# Sheet1.net
KiCad netlist of a schematic drawn in Altium Designer
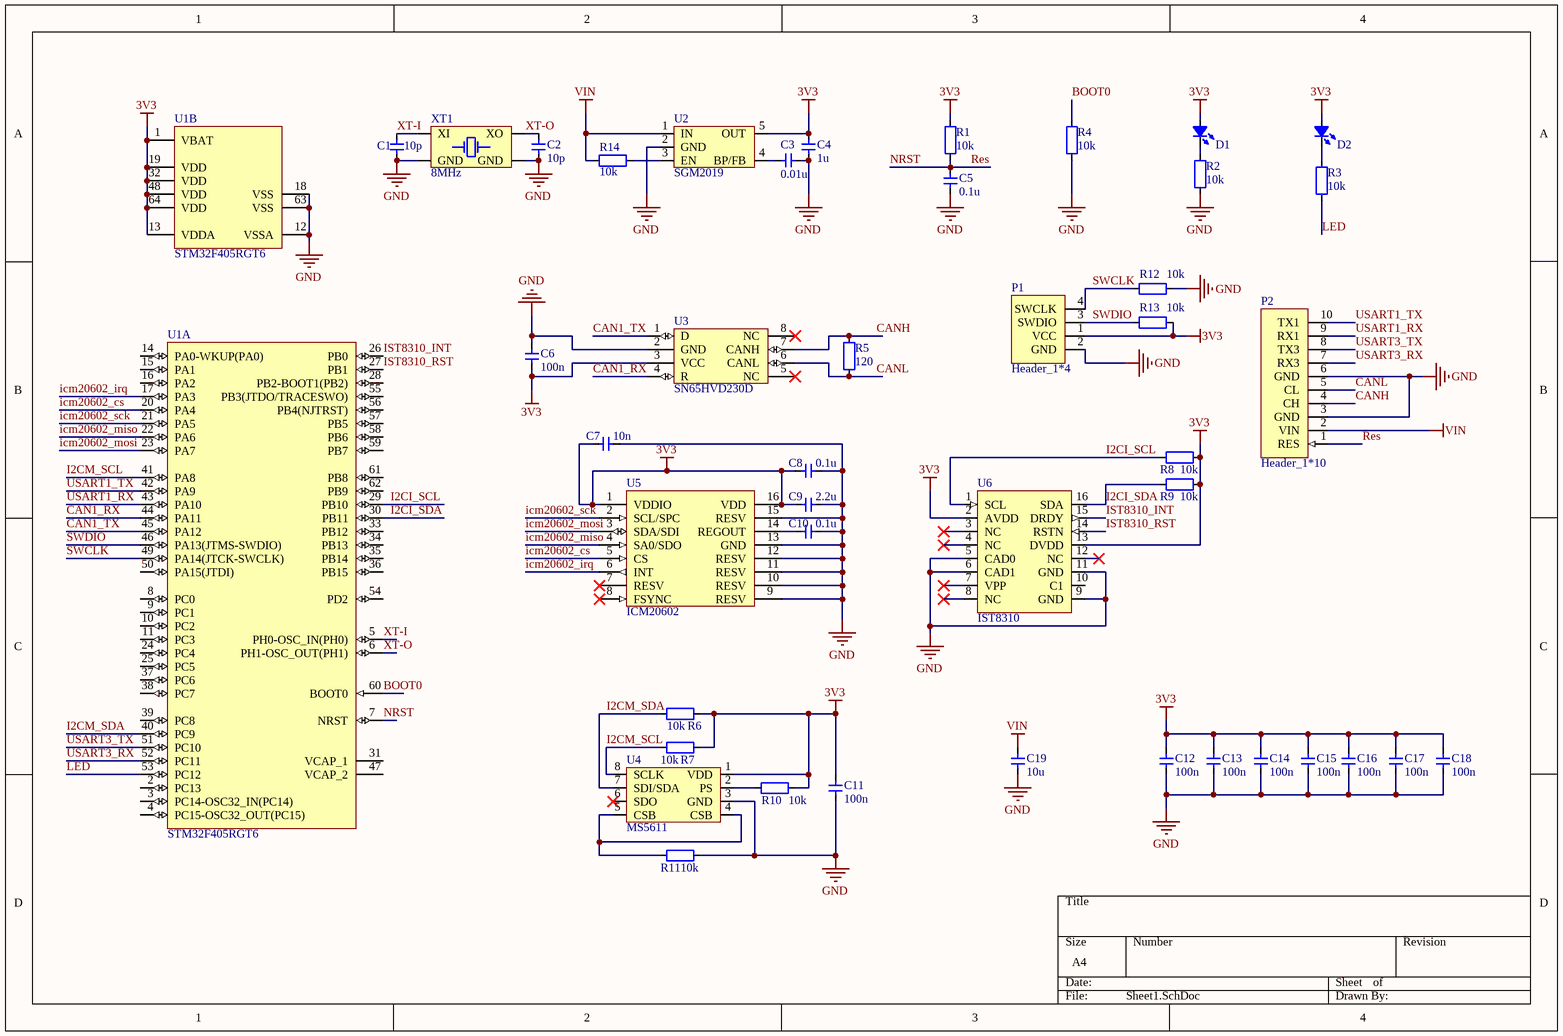
[diagram p0: Sheet1.SchDoc]

(export (version "E")
  (design (tool "Eeschema 10.0.6"))
  (components
    (comp (ref "C1")
      (value "10p")
      (footprint "CAP_0603")
      (description "Capacitor")
      (fields (field (name "Comment") "Cap_0603"))
      (libsource (lib "Schlib1") (part "Cap_0603"))
    )
    (comp (ref "C2")
      (value "10p")
      (footprint "CAP_0603")
      (description "Capacitor")
      (fields (field (name "Comment") "Cap_0603"))
      (libsource (lib "Schlib1") (part "Cap_0603"))
    )
    (comp (ref "C3")
      (value "0.01u")
      (footprint "CAP_0603")
      (description "Capacitor")
      (fields (field (name "Comment") "Cap_0603"))
      (libsource (lib "Schlib1") (part "Cap_0603"))
    )
    (comp (ref "C4")
      (value "1u")
      (footprint "CAP_0603")
      (description "Capacitor")
      (fields (field (name "Comment") "Cap_0603"))
      (libsource (lib "Schlib1") (part "Cap_0603"))
    )
    (comp (ref "C5")
      (value "0.1u")
      (footprint "CAP_0603")
      (description "Capacitor")
      (fields (field (name "Comment") "Cap_0603"))
      (libsource (lib "Schlib1") (part "Cap_0603"))
    )
    (comp (ref "C6")
      (value "100n")
      (footprint "CAP_0603")
      (description "Capacitor")
      (fields (field (name "Comment") "Cap_0603"))
      (libsource (lib "Schlib1") (part "Cap_0603"))
    )
    (comp (ref "C7")
      (value "10n")
      (footprint "CAP_0603")
      (description "Capacitor")
      (fields (field (name "Comment") "Cap_0603"))
      (libsource (lib "Schlib1") (part "Cap_0603"))
    )
    (comp (ref "C8")
      (value "0.1u")
      (footprint "CAP_0603")
      (description "Capacitor")
      (fields (field (name "Comment") "Cap_0603"))
      (libsource (lib "Schlib1") (part "Cap_0603"))
    )
    (comp (ref "C9")
      (value "2.2u")
      (footprint "CAP_0603")
      (description "Capacitor")
      (fields (field (name "Comment") "Cap_0603"))
      (libsource (lib "Schlib1") (part "Cap_0603"))
    )
    (comp (ref "C10")
      (value "0.1u")
      (footprint "CAP_0603")
      (description "Capacitor")
      (fields (field (name "Comment") "Cap_0603"))
      (libsource (lib "Schlib1") (part "Cap_0603"))
    )
    (comp (ref "C11")
      (value "100n")
      (footprint "CAP_0603")
      (description "Capacitor")
      (fields (field (name "Comment") "Cap_0603"))
      (libsource (lib "Schlib1") (part "Cap_0603"))
    )
    (comp (ref "C12")
      (value "100n")
      (footprint "CAP_0603")
      (description "Capacitor")
      (fields (field (name "Comment") "Cap_0603"))
      (libsource (lib "Schlib1") (part "Cap_0603"))
    )
    (comp (ref "C13")
      (value "100n")
      (footprint "CAP_0603")
      (description "Capacitor")
      (fields (field (name "Comment") "Cap_0603"))
      (libsource (lib "Schlib1") (part "Cap_0603"))
    )
    (comp (ref "C14")
      (value "100n")
      (footprint "CAP_0603")
      (description "Capacitor")
      (fields (field (name "Comment") "Cap_0603"))
      (libsource (lib "Schlib1") (part "Cap_0603"))
    )
    (comp (ref "C15")
      (value "100n")
      (footprint "CAP_0603")
      (description "Capacitor")
      (fields (field (name "Comment") "Cap_0603"))
      (libsource (lib "Schlib1") (part "Cap_0603"))
    )
    (comp (ref "C16")
      (value "100n")
      (footprint "CAP_0603")
      (description "Capacitor")
      (fields (field (name "Comment") "Cap_0603"))
      (libsource (lib "Schlib1") (part "Cap_0603"))
    )
    (comp (ref "C17")
      (value "100n")
      (footprint "CAP_0603")
      (description "Capacitor")
      (fields (field (name "Comment") "Cap_0603"))
      (libsource (lib "Schlib1") (part "Cap_0603"))
    )
    (comp (ref "C18")
      (value "100n")
      (footprint "CAP_0603")
      (description "Capacitor")
      (fields (field (name "Comment") "Cap_0603"))
      (libsource (lib "Schlib1") (part "Cap_0603"))
    )
    (comp (ref "C19")
      (value "10u")
      (footprint "CAP_0805")
      (description "Capacitor")
      (fields (field (name "Comment") "Cap_0805"))
      (libsource (lib "Schlib1") (part "Cap_0805"))
    )
    (comp (ref "D1")
      (value "LED_0603")
      (footprint "LED_0603")
      (description "LED")
      (libsource (lib "Schlib1") (part "LED_0603"))
    )
    (comp (ref "D2")
      (value "LED_0603")
      (footprint "LED_0603")
      (description "LED")
      (libsource (lib "Schlib1") (part "LED_0603"))
    )
    (comp (ref "P1")
      (value "Header_1*4")
      (footprint "HDR1*4")
      (libsource (lib "Schlib1") (part "Header_1*4"))
    )
    (comp (ref "P2")
      (value "Header_1*10")
      (footprint "HDR1*10")
      (libsource (lib "Schlib1") (part "Header_1*10"))
    )
    (comp (ref "R1")
      (value "10k")
      (footprint "RES_0603")
      (description "Resistor")
      (fields (field (name "Comment") "Res_0603"))
      (libsource (lib "") (part "Res_0603_2"))
    )
    (comp (ref "R2")
      (value "10k")
      (footprint "RES_0603")
      (description "Resistor")
      (fields (field (name "Comment") "Res_0603"))
      (libsource (lib "") (part "Res_0603_2"))
    )
    (comp (ref "R3")
      (value "10k")
      (footprint "RES_0603")
      (description "Resistor")
      (fields (field (name "Comment") "Res_0603"))
      (libsource (lib "") (part "Res_0603_2"))
    )
    (comp (ref "R4")
      (value "10k")
      (footprint "RES_0603")
      (description "Resistor")
      (fields (field (name "Comment") "Res_0603"))
      (libsource (lib "") (part "Res_0603_2"))
    )
    (comp (ref "R5")
      (value "120")
      (footprint "RES_0603")
      (description "Resistor")
      (fields (field (name "Comment") "Res_0603"))
      (libsource (lib "") (part "Res_0603_2"))
    )
    (comp (ref "R6")
      (value "10k")
      (footprint "RES_0603")
      (description "Resistor")
      (fields (field (name "Comment") "Res_0603"))
      (libsource (lib "Schlib1") (part "Res_0603"))
    )
    (comp (ref "R7")
      (value "10k")
      (footprint "RES_0603")
      (description "Resistor")
      (fields (field (name "Comment") "Res_0603"))
      (libsource (lib "Schlib1") (part "Res_0603"))
    )
    (comp (ref "R8")
      (value "10k")
      (footprint "RES_0603")
      (description "Resistor")
      (fields (field (name "Comment") "Res_0603"))
      (libsource (lib "Schlib1") (part "Res_0603"))
    )
    (comp (ref "R9")
      (value "10k")
      (footprint "RES_0603")
      (description "Resistor")
      (fields (field (name "Comment") "Res_0603"))
      (libsource (lib "Schlib1") (part "Res_0603"))
    )
    (comp (ref "R10")
      (value "10k")
      (footprint "RES_0603")
      (description "Resistor")
      (fields (field (name "Comment") "Res_0603"))
      (libsource (lib "Schlib1") (part "Res_0603"))
    )
    (comp (ref "R11")
      (value "10k")
      (footprint "RES_0603")
      (description "Resistor")
      (fields (field (name "Comment") "Res_0603"))
      (libsource (lib "Schlib1") (part "Res_0603"))
    )
    (comp (ref "R12")
      (value "10k")
      (footprint "RES_0603")
      (description "Resistor")
      (fields (field (name "Comment") "Res_0603"))
      (libsource (lib "") (part "Res_0603_1"))
    )
    (comp (ref "R13")
      (value "10k")
      (footprint "RES_0603")
      (description "Resistor")
      (fields (field (name "Comment") "Res_0603"))
      (libsource (lib "") (part "Res_0603_1"))
    )
    (comp (ref "R14")
      (value "10k")
      (footprint "RES_0603")
      (description "Resistor")
      (fields (field (name "Comment") "Res_0603"))
      (libsource (lib "Schlib1") (part "Res_0603"))
    )
    (comp (ref "U1")
      (value "STM32F405RGT6")
      (footprint "STM-LQFP64_N")
      (fields (field (name "MANUFACTURER") "STMicroelectronics"))
      (libsource (lib "STMicroelectronics STM32 F4") (part "STM32F405RGT6"))
    )
    (comp (ref "U2") (value "SGM2019") (footprint "SGM2019") (libsource (lib "Schlib1") (part "SGM2019")))
    (comp (ref "U3")
      (value "SN65HVD230D")
      (footprint "SN65HVD230")
      (libsource (lib "Schlib1") (part "SN65HVD230D"))
    )
    (comp (ref "U4") (value "MS5611") (footprint "MS5611") (libsource (lib "Schlib1") (part "MS5611")))
    (comp (ref "U5") (value "ICM20602") (footprint "ICM20602") (libsource (lib "Schlib1") (part "ICM20602")))
    (comp (ref "U6") (value "IST8310") (footprint "IST8310") (libsource (lib "Schlib1") (part "IST8310")))
    (comp (ref "XT1")
      (value "8MHz")
      (footprint "XT_2520_4")
      (description "Crystal Oscillator")
      (fields (field (name "Comment") "XTAL_2520_4P"))
      (libsource (lib "Schlib1") (part "XTAL_2520_4P"))
    )
  )
  (nets
    (net (code "1") (name "/BOOT0") (class "Default")
      (node (ref "R4") (pin "1") (pinfunction "1_1") (pintype "passive"))
      (node (ref "U1") (pin "60") (pinfunction "BOOT0_60") (pintype "input"))
    )
    (net (code "2") (name "/CAN1_RX") (class "Default")
      (node (ref "U1") (pin "44") (pinfunction "PA11_44") (pintype "bidirectional"))
      (node (ref "U3") (pin "4") (pinfunction "R_4") (pintype "bidirectional"))
    )
    (net (code "3") (name "/CAN1_TX") (class "Default")
      (node (ref "U1") (pin "45") (pinfunction "PA12_45") (pintype "bidirectional"))
      (node (ref "U3") (pin "1") (pinfunction "D_1") (pintype "bidirectional"))
    )
    (net (code "4") (name "/CANH") (class "Default")
      (node (ref "P2") (pin "4") (pinfunction "CH_4") (pintype "passive"))
      (node (ref "R5") (pin "1") (pinfunction "1_1") (pintype "passive"))
      (node (ref "U3") (pin "7") (pinfunction "CANH_7") (pintype "bidirectional"))
    )
    (net (code "5") (name "/CANL") (class "Default")
      (node (ref "P2") (pin "5") (pinfunction "CL_5") (pintype "passive"))
      (node (ref "R5") (pin "2") (pinfunction "2_2") (pintype "passive"))
      (node (ref "U3") (pin "6") (pinfunction "CANL_6") (pintype "bidirectional"))
    )
    (net (code "6") (name "/I2CI_SCL") (class "Default")
      (node (ref "R8") (pin "1") (pinfunction "1_1") (pintype "passive"))
      (node (ref "U1") (pin "29") (pinfunction "PB10_29") (pintype "bidirectional"))
      (node (ref "U6") (pin "1") (pinfunction "SCL_1") (pintype "input"))
    )
    (net (code "7") (name "/I2CI_SDA") (class "Default")
      (node (ref "R9") (pin "1") (pinfunction "1_1") (pintype "passive"))
      (node (ref "U1") (pin "30") (pinfunction "PB11_30") (pintype "bidirectional"))
      (node (ref "U6") (pin "16") (pinfunction "SDA_16") (pintype "bidirectional"))
    )
    (net (code "8") (name "/I2CM_SCL") (class "Default")
      (node (ref "R7") (pin "1") (pinfunction "1_1") (pintype "passive"))
      (node (ref "U1") (pin "41") (pinfunction "PA8_41") (pintype "bidirectional"))
      (node (ref "U4") (pin "8") (pinfunction "SCLK_8") (pintype "passive"))
    )
    (net (code "9") (name "/I2CM_SDA") (class "Default")
      (node (ref "R6") (pin "1") (pinfunction "1_1") (pintype "passive"))
      (node (ref "U1") (pin "40") (pinfunction "PC9_40") (pintype "bidirectional"))
      (node (ref "U4") (pin "7") (pinfunction "SDI/SDA_7") (pintype "passive"))
    )
    (net (code "10") (name "/IST8310_INT") (class "Default")
      (node (ref "U1") (pin "26") (pinfunction "PB0_26") (pintype "bidirectional"))
      (node (ref "U6") (pin "15") (pinfunction "DRDY_15") (pintype "output"))
    )
    (net (code "11") (name "/IST8310_RST") (class "Default")
      (node (ref "U1") (pin "27") (pinfunction "PB1_27") (pintype "bidirectional"))
      (node (ref "U6") (pin "14") (pinfunction "RSTN_14") (pintype "input"))
    )
    (net (code "12") (name "/LED") (class "Default")
      (node (ref "R3") (pin "2") (pinfunction "2_2") (pintype "passive"))
      (node (ref "U1") (pin "53") (pinfunction "PC12_53") (pintype "bidirectional"))
    )
    (net (code "13") (name "/NRST") (class "Default")
      (node (ref "C5") (pin "2") (pinfunction "2_2") (pintype "passive"))
      (node (ref "P2") (pin "1") (pinfunction "RES_1") (pintype "input"))
      (node (ref "R1") (pin "2") (pinfunction "2_2") (pintype "passive"))
      (node (ref "U1") (pin "7") (pinfunction "NRST_7") (pintype "bidirectional"))
    )
    (net (code "14") (name "/SWCLK") (class "Default")
      (node (ref "P1") (pin "4") (pinfunction "SWCLK_4") (pintype "passive"))
      (node (ref "R12") (pin "2") (pinfunction "2_2") (pintype "passive"))
      (node (ref "U1") (pin "49") (pinfunction "PA14(JTCK-SWCLK)_49") (pintype "bidirectional"))
    )
    (net (code "15") (name "/SWDIO") (class "Default")
      (node (ref "P1") (pin "3") (pinfunction "SWDIO_3") (pintype "passive"))
      (node (ref "R13") (pin "2") (pinfunction "2_2") (pintype "passive"))
      (node (ref "U1") (pin "46") (pinfunction "PA13(JTMS-SWDIO)_46") (pintype "bidirectional"))
    )
    (net (code "16") (name "/USART1_RX") (class "Default")
      (node (ref "P2") (pin "9") (pinfunction "RX1_9") (pintype "passive"))
      (node (ref "U1") (pin "43") (pinfunction "PA10_43") (pintype "bidirectional"))
    )
    (net (code "17") (name "/USART1_TX") (class "Default")
      (node (ref "P2") (pin "10") (pinfunction "TX1_10") (pintype "passive"))
      (node (ref "U1") (pin "42") (pinfunction "PA9_42") (pintype "bidirectional"))
    )
    (net (code "18") (name "/USART3_RX") (class "Default")
      (node (ref "P2") (pin "7") (pinfunction "RX3_7") (pintype "passive"))
      (node (ref "U1") (pin "52") (pinfunction "PC11_52") (pintype "bidirectional"))
    )
    (net (code "19") (name "/USART3_TX") (class "Default")
      (node (ref "P2") (pin "8") (pinfunction "TX3_8") (pintype "passive"))
      (node (ref "U1") (pin "51") (pinfunction "PC10_51") (pintype "bidirectional"))
    )
    (net (code "20") (name "/XT-I") (class "Default")
      (node (ref "C1") (pin "2") (pinfunction "2_2") (pintype "passive"))
      (node (ref "U1") (pin "5") (pinfunction "PH0-OSC_IN(PH0)_5") (pintype "bidirectional"))
      (node (ref "XT1") (pin "1") (pinfunction "XI_1") (pintype "passive"))
    )
    (net (code "21") (name "/XT-O") (class "Default")
      (node (ref "C2") (pin "2") (pinfunction "2_2") (pintype "passive"))
      (node (ref "U1") (pin "6") (pinfunction "PH1-OSC_OUT(PH1)_6") (pintype "bidirectional"))
      (node (ref "XT1") (pin "3") (pinfunction "XO_3") (pintype "passive"))
    )
    (net (code "22") (name "/icm20602_cs") (class "Default")
      (node (ref "U1") (pin "20") (pinfunction "PA4_20") (pintype "bidirectional"))
      (node (ref "U5") (pin "5") (pinfunction "CS_5") (pintype "input"))
    )
    (net (code "23") (name "/icm20602_irq") (class "Default")
      (node (ref "U1") (pin "17") (pinfunction "PA3_17") (pintype "bidirectional"))
      (node (ref "U5") (pin "6") (pinfunction "INT_6") (pintype "output"))
    )
    (net (code "24") (name "/icm20602_miso") (class "Default")
      (node (ref "U1") (pin "22") (pinfunction "PA6_22") (pintype "bidirectional"))
      (node (ref "U5") (pin "4") (pinfunction "SA0/SDO_4") (pintype "input"))
    )
    (net (code "25") (name "/icm20602_mosi") (class "Default")
      (node (ref "U1") (pin "23") (pinfunction "PA7_23") (pintype "bidirectional"))
      (node (ref "U5") (pin "3") (pinfunction "SDA/SDI_3") (pintype "bidirectional"))
    )
    (net (code "26") (name "/icm20602_sck") (class "Default")
      (node (ref "U1") (pin "21") (pinfunction "PA5_21") (pintype "bidirectional"))
      (node (ref "U5") (pin "2") (pinfunction "SCL/SPC_2") (pintype "input"))
    )
    (net (code "27") (name "3V3") (class "Default")
      (node (ref "C11") (pin "2") (pinfunction "2_2") (pintype "passive"))
      (node (ref "C12") (pin "2") (pinfunction "2_2") (pintype "passive"))
      (node (ref "C13") (pin "2") (pinfunction "2_2") (pintype "passive"))
      (node (ref "C14") (pin "2") (pinfunction "2_2") (pintype "passive"))
      (node (ref "C15") (pin "2") (pinfunction "2_2") (pintype "passive"))
      (node (ref "C16") (pin "2") (pinfunction "2_2") (pintype "passive"))
      (node (ref "C17") (pin "2") (pinfunction "2_2") (pintype "passive"))
      (node (ref "C18") (pin "2") (pinfunction "2_2") (pintype "passive"))
      (node (ref "C4") (pin "2") (pinfunction "2_2") (pintype "passive"))
      (node (ref "C6") (pin "1") (pinfunction "1_1") (pintype "passive"))
      (node (ref "C7") (pin "2") (pinfunction "2_2") (pintype "passive"))
      (node (ref "C8") (pin "2") (pinfunction "2_2") (pintype "passive"))
      (node (ref "C9") (pin "2") (pinfunction "2_2") (pintype "passive"))
      (node (ref "D1") (pin "1") (pinfunction "A_1") (pintype "passive"))
      (node (ref "D2") (pin "1") (pinfunction "A_1") (pintype "passive"))
      (node (ref "P1") (pin "1") (pinfunction "VCC_1") (pintype "power_in"))
      (node (ref "R1") (pin "1") (pinfunction "1_1") (pintype "passive"))
      (node (ref "R10") (pin "2") (pinfunction "2_2") (pintype "passive"))
      (node (ref "R13") (pin "1") (pinfunction "1_1") (pintype "passive"))
      (node (ref "R6") (pin "2") (pinfunction "2_2") (pintype "passive"))
      (node (ref "R7") (pin "2") (pinfunction "2_2") (pintype "passive"))
      (node (ref "R8") (pin "2") (pinfunction "2_2") (pintype "passive"))
      (node (ref "R9") (pin "2") (pinfunction "2_2") (pintype "passive"))
      (node (ref "U1") (pin "1") (pinfunction "VBAT_1") (pintype "power_in"))
      (node (ref "U1") (pin "13") (pinfunction "VDDA_13") (pintype "power_in"))
      (node (ref "U1") (pin "19") (pinfunction "VDD_19") (pintype "power_in"))
      (node (ref "U1") (pin "32") (pinfunction "VDD_32") (pintype "power_in"))
      (node (ref "U1") (pin "48") (pinfunction "VDD_48") (pintype "power_in"))
      (node (ref "U1") (pin "64") (pinfunction "VDD_64") (pintype "power_in"))
      (node (ref "U2") (pin "5") (pinfunction "OUT_5") (pintype "passive"))
      (node (ref "U3") (pin "3") (pinfunction "VCC_3") (pintype "power_in"))
      (node (ref "U4") (pin "1") (pinfunction "VDD_1") (pintype "power_in"))
      (node (ref "U5") (pin "1") (pinfunction "VDDIO_1") (pintype "passive"))
      (node (ref "U5") (pin "16") (pinfunction "VDD_16") (pintype "power_in"))
      (node (ref "U6") (pin "13") (pinfunction "DVDD_13") (pintype "power_in"))
      (node (ref "U6") (pin "2") (pinfunction "AVDD_2") (pintype "power_in"))
    )
    (net (code "28") (name "GND") (class "Default")
      (node (ref "C1") (pin "1") (pinfunction "1_1") (pintype "passive"))
      (node (ref "C10") (pin "1") (pinfunction "1_1") (pintype "passive"))
      (node (ref "C11") (pin "1") (pinfunction "1_1") (pintype "passive"))
      (node (ref "C12") (pin "1") (pinfunction "1_1") (pintype "passive"))
      (node (ref "C13") (pin "1") (pinfunction "1_1") (pintype "passive"))
      (node (ref "C14") (pin "1") (pinfunction "1_1") (pintype "passive"))
      (node (ref "C15") (pin "1") (pinfunction "1_1") (pintype "passive"))
      (node (ref "C16") (pin "1") (pinfunction "1_1") (pintype "passive"))
      (node (ref "C17") (pin "1") (pinfunction "1_1") (pintype "passive"))
      (node (ref "C18") (pin "1") (pinfunction "1_1") (pintype "passive"))
      (node (ref "C19") (pin "1") (pinfunction "1_1") (pintype "passive"))
      (node (ref "C2") (pin "1") (pinfunction "1_1") (pintype "passive"))
      (node (ref "C3") (pin "1") (pinfunction "1_1") (pintype "passive"))
      (node (ref "C4") (pin "1") (pinfunction "1_1") (pintype "passive"))
      (node (ref "C5") (pin "1") (pinfunction "1_1") (pintype "passive"))
      (node (ref "C6") (pin "2") (pinfunction "2_2") (pintype "passive"))
      (node (ref "C7") (pin "1") (pinfunction "1_1") (pintype "passive"))
      (node (ref "C8") (pin "1") (pinfunction "1_1") (pintype "passive"))
      (node (ref "C9") (pin "1") (pinfunction "1_1") (pintype "passive"))
      (node (ref "P1") (pin "2") (pinfunction "GND_2") (pintype "power_in"))
      (node (ref "P2") (pin "3") (pinfunction "GND_3") (pintype "passive"))
      (node (ref "P2") (pin "6") (pinfunction "GND_6") (pintype "passive"))
      (node (ref "R11") (pin "2") (pinfunction "2_2") (pintype "passive"))
      (node (ref "R12") (pin "1") (pinfunction "1_1") (pintype "passive"))
      (node (ref "R2") (pin "2") (pinfunction "2_2") (pintype "passive"))
      (node (ref "R4") (pin "2") (pinfunction "2_2") (pintype "passive"))
      (node (ref "U1") (pin "12") (pinfunction "VSSA_12") (pintype "power_in"))
      (node (ref "U1") (pin "18") (pinfunction "VSS_18") (pintype "power_in"))
      (node (ref "U1") (pin "63") (pinfunction "VSS_63") (pintype "power_in"))
      (node (ref "U2") (pin "2") (pinfunction "GND_2") (pintype "passive"))
      (node (ref "U3") (pin "2") (pinfunction "GND_2") (pintype "power_in"))
      (node (ref "U4") (pin "3") (pinfunction "GND_3") (pintype "power_in"))
      (node (ref "U5") (pin "10") (pinfunction "RESV_10") (pintype "passive"))
      (node (ref "U5") (pin "11") (pinfunction "RESV_11") (pintype "passive"))
      (node (ref "U5") (pin "12") (pinfunction "RESV_12") (pintype "passive"))
      (node (ref "U5") (pin "13") (pinfunction "GND_13") (pintype "power_in"))
      (node (ref "U5") (pin "15") (pinfunction "RESV_15") (pintype "passive"))
      (node (ref "U5") (pin "9") (pinfunction "RESV_9") (pintype "passive"))
      (node (ref "U6") (pin "11") (pinfunction "GND_11") (pintype "power_in"))
      (node (ref "U6") (pin "5") (pinfunction "CAD0_5") (pintype "passive"))
      (node (ref "U6") (pin "6") (pinfunction "CAD1_6") (pintype "passive"))
      (node (ref "U6") (pin "9") (pinfunction "GND_9") (pintype "power_in"))
      (node (ref "XT1") (pin "2") (pinfunction "GND_2") (pintype "power_in"))
      (node (ref "XT1") (pin "4") (pinfunction "GND_4") (pintype "power_in"))
    )
    (net (code "29") (name "Net-(D1-K)") (class "Default")
      (node (ref "D1") (pin "2") (pinfunction "K_2") (pintype "passive"))
      (node (ref "R2") (pin "1") (pinfunction "1_1") (pintype "passive"))
    )
    (net (code "30") (name "Net-(D2-K)") (class "Default")
      (node (ref "D2") (pin "2") (pinfunction "K_2") (pintype "passive"))
      (node (ref "R3") (pin "1") (pinfunction "1_1") (pintype "passive"))
    )
    (net (code "31") (name "Net-(R11-Pad1)") (class "Default")
      (node (ref "R11") (pin "1") (pinfunction "1_1") (pintype "passive"))
      (node (ref "U4") (pin "4") (pinfunction "CSB_4") (pintype "passive"))
      (node (ref "U4") (pin "5") (pinfunction "CSB_5") (pintype "passive"))
    )
    (net (code "32") (name "Net-(U2-BP{slash}FB)") (class "Default")
      (node (ref "C3") (pin "2") (pinfunction "2_2") (pintype "passive"))
      (node (ref "U2") (pin "4") (pinfunction "BP/FB_4") (pintype "passive"))
    )
    (net (code "33") (name "Net-(U2-EN)") (class "Default")
      (node (ref "R14") (pin "2") (pinfunction "2_2") (pintype "passive"))
      (node (ref "U2") (pin "3") (pinfunction "EN_3") (pintype "passive"))
    )
    (net (code "34") (name "Net-(U4-PS)") (class "Default")
      (node (ref "R10") (pin "1") (pinfunction "1_1") (pintype "passive"))
      (node (ref "U4") (pin "2") (pinfunction "PS_2") (pintype "passive"))
    )
    (net (code "35") (name "Net-(U5-REGOUT)") (class "Default")
      (node (ref "C10") (pin "2") (pinfunction "2_2") (pintype "passive"))
      (node (ref "U5") (pin "14") (pinfunction "REGOUT_14") (pintype "passive"))
    )
    (net (code "36") (name "VIN") (class "Default")
      (node (ref "C19") (pin "2") (pinfunction "2_2") (pintype "passive"))
      (node (ref "P2") (pin "2") (pinfunction "VIN_2") (pintype "power_in"))
      (node (ref "R14") (pin "1") (pinfunction "1_1") (pintype "passive"))
      (node (ref "U2") (pin "1") (pinfunction "IN_1") (pintype "passive"))
    )
    (net (code "37") (name "unconnected-(U1A-PA0-WKUP(PA0)-Pad14)") (class "Default")
      (node (ref "U1") (pin "14") (pinfunction "PA0-WKUP(PA0)_14") (pintype "bidirectional"))
    )
    (net (code "38") (name "unconnected-(U1A-PA1-Pad15)") (class "Default")
      (node (ref "U1") (pin "15") (pinfunction "PA1_15") (pintype "bidirectional"))
    )
    (net (code "39") (name "unconnected-(U1A-PA2-Pad16)") (class "Default")
      (node (ref "U1") (pin "16") (pinfunction "PA2_16") (pintype "bidirectional"))
    )
    (net (code "40") (name "unconnected-(U1A-PA15(JTDI)-Pad50)") (class "Default")
      (node (ref "U1") (pin "50") (pinfunction "PA15(JTDI)_50") (pintype "bidirectional"))
    )
    (net (code "41") (name "unconnected-(U1A-PB2-BOOT1(PB2)-Pad28)") (class "Default")
      (node (ref "U1") (pin "28") (pinfunction "PB2-BOOT1(PB2)_28") (pintype "bidirectional"))
    )
    (net (code "42") (name "unconnected-(U1A-PB3(JTDO{slash}TRACESWO)-Pad55)") (class "Default")
      (node (ref "U1") (pin "55") (pinfunction "PB3(JTDO/TRACESWO)_55") (pintype "bidirectional"))
    )
    (net (code "43") (name "unconnected-(U1A-PB4(NJTRST)-Pad56)") (class "Default")
      (node (ref "U1") (pin "56") (pinfunction "PB4(NJTRST)_56") (pintype "bidirectional"))
    )
    (net (code "44") (name "unconnected-(U1A-PB5-Pad57)") (class "Default")
      (node (ref "U1") (pin "57") (pinfunction "PB5_57") (pintype "bidirectional"))
    )
    (net (code "45") (name "unconnected-(U1A-PB6-Pad58)") (class "Default")
      (node (ref "U1") (pin "58") (pinfunction "PB6_58") (pintype "bidirectional"))
    )
    (net (code "46") (name "unconnected-(U1A-PB7-Pad59)") (class "Default")
      (node (ref "U1") (pin "59") (pinfunction "PB7_59") (pintype "bidirectional"))
    )
    (net (code "47") (name "unconnected-(U1A-PB8-Pad61)") (class "Default")
      (node (ref "U1") (pin "61") (pinfunction "PB8_61") (pintype "bidirectional"))
    )
    (net (code "48") (name "unconnected-(U1A-PB9-Pad62)") (class "Default")
      (node (ref "U1") (pin "62") (pinfunction "PB9_62") (pintype "bidirectional"))
    )
    (net (code "49") (name "unconnected-(U1A-PB12-Pad33)") (class "Default")
      (node (ref "U1") (pin "33") (pinfunction "PB12_33") (pintype "bidirectional"))
    )
    (net (code "50") (name "unconnected-(U1A-PB13-Pad34)") (class "Default")
      (node (ref "U1") (pin "34") (pinfunction "PB13_34") (pintype "bidirectional"))
    )
    (net (code "51") (name "unconnected-(U1A-PB14-Pad35)") (class "Default")
      (node (ref "U1") (pin "35") (pinfunction "PB14_35") (pintype "bidirectional"))
    )
    (net (code "52") (name "unconnected-(U1A-PB15-Pad36)") (class "Default")
      (node (ref "U1") (pin "36") (pinfunction "PB15_36") (pintype "bidirectional"))
    )
    (net (code "53") (name "unconnected-(U1A-PC0-Pad8)") (class "Default")
      (node (ref "U1") (pin "8") (pinfunction "PC0_8") (pintype "bidirectional"))
    )
    (net (code "54") (name "unconnected-(U1A-PC1-Pad9)") (class "Default")
      (node (ref "U1") (pin "9") (pinfunction "PC1_9") (pintype "bidirectional"))
    )
    (net (code "55") (name "unconnected-(U1A-PC2-Pad10)") (class "Default")
      (node (ref "U1") (pin "10") (pinfunction "PC2_10") (pintype "bidirectional"))
    )
    (net (code "56") (name "unconnected-(U1A-PC3-Pad11)") (class "Default")
      (node (ref "U1") (pin "11") (pinfunction "PC3_11") (pintype "bidirectional"))
    )
    (net (code "57") (name "unconnected-(U1A-PC4-Pad24)") (class "Default")
      (node (ref "U1") (pin "24") (pinfunction "PC4_24") (pintype "bidirectional"))
    )
    (net (code "58") (name "unconnected-(U1A-PC5-Pad25)") (class "Default")
      (node (ref "U1") (pin "25") (pinfunction "PC5_25") (pintype "bidirectional"))
    )
    (net (code "59") (name "unconnected-(U1A-PC6-Pad37)") (class "Default")
      (node (ref "U1") (pin "37") (pinfunction "PC6_37") (pintype "bidirectional"))
    )
    (net (code "60") (name "unconnected-(U1A-PC7-Pad38)") (class "Default")
      (node (ref "U1") (pin "38") (pinfunction "PC7_38") (pintype "bidirectional"))
    )
    (net (code "61") (name "unconnected-(U1A-PC8-Pad39)") (class "Default")
      (node (ref "U1") (pin "39") (pinfunction "PC8_39") (pintype "bidirectional"))
    )
    (net (code "62") (name "unconnected-(U1A-PC13-Pad2)") (class "Default")
      (node (ref "U1") (pin "2") (pinfunction "PC13_2") (pintype "bidirectional"))
    )
    (net (code "63") (name "unconnected-(U1A-PC14-OSC32_IN(PC14)-Pad3)") (class "Default")
      (node (ref "U1") (pin "3") (pinfunction "PC14-OSC32_IN(PC14)_3") (pintype "bidirectional"))
    )
    (net (code "64") (name "unconnected-(U1A-PC15-OSC32_OUT(PC15)-Pad4)") (class "Default")
      (node (ref "U1") (pin "4") (pinfunction "PC15-OSC32_OUT(PC15)_4") (pintype "bidirectional"))
    )
    (net (code "65") (name "unconnected-(U1A-PD2-Pad54)") (class "Default")
      (node (ref "U1") (pin "54") (pinfunction "PD2_54") (pintype "bidirectional"))
    )
    (net (code "66") (name "unconnected-(U1A-VCAP_1-Pad31)") (class "Default")
      (node (ref "U1") (pin "31") (pinfunction "VCAP_1_31") (pintype "power_in"))
    )
    (net (code "67") (name "unconnected-(U1A-VCAP_2-Pad47)") (class "Default")
      (node (ref "U1") (pin "47") (pinfunction "VCAP_2_47") (pintype "power_in"))
    )
    (net (code "68") (name "unconnected-(U3-NC-Pad5)") (class "Default")
      (node (ref "U3") (pin "5") (pinfunction "NC_5") (pintype "passive+no_connect"))
    )
    (net (code "69") (name "unconnected-(U3-NC-Pad8)") (class "Default")
      (node (ref "U3") (pin "8") (pinfunction "NC_8") (pintype "passive+no_connect"))
    )
    (net (code "70") (name "unconnected-(U4-SDO-Pad6)") (class "Default")
      (node (ref "U4") (pin "6") (pinfunction "SDO_6") (pintype "passive+no_connect"))
    )
    (net (code "71") (name "unconnected-(U5-FSYNC-Pad8)") (class "Default")
      (node (ref "U5") (pin "8") (pinfunction "FSYNC_8") (pintype "input+no_connect"))
    )
    (net (code "72") (name "unconnected-(U5-RESV-Pad7)") (class "Default")
      (node (ref "U5") (pin "7") (pinfunction "RESV_7") (pintype "passive+no_connect"))
    )
    (net (code "73") (name "unconnected-(U6-C1-Pad10)") (class "Default")
      (node (ref "U6") (pin "10") (pinfunction "C1_10") (pintype "passive"))
    )
    (net (code "74") (name "unconnected-(U6-NC-Pad3)") (class "Default")
      (node (ref "U6") (pin "3") (pinfunction "NC_3") (pintype "passive+no_connect"))
    )
    (net (code "75") (name "unconnected-(U6-NC-Pad4)") (class "Default")
      (node (ref "U6") (pin "4") (pinfunction "NC_4") (pintype "passive+no_connect"))
    )
    (net (code "76") (name "unconnected-(U6-NC-Pad8)") (class "Default")
      (node (ref "U6") (pin "8") (pinfunction "NC_8") (pintype "passive+no_connect"))
    )
    (net (code "77") (name "unconnected-(U6-NC-Pad12)") (class "Default")
      (node (ref "U6") (pin "12") (pinfunction "NC_12") (pintype "passive+no_connect"))
    )
    (net (code "78") (name "unconnected-(U6-VPP-Pad7)") (class "Default")
      (node (ref "U6") (pin "7") (pinfunction "VPP_7") (pintype "passive+no_connect"))
    )
  )
)
